# SCH_Aether_Zero_R0_4.net
KiCad netlist of a schematic drawn in EasyEDA
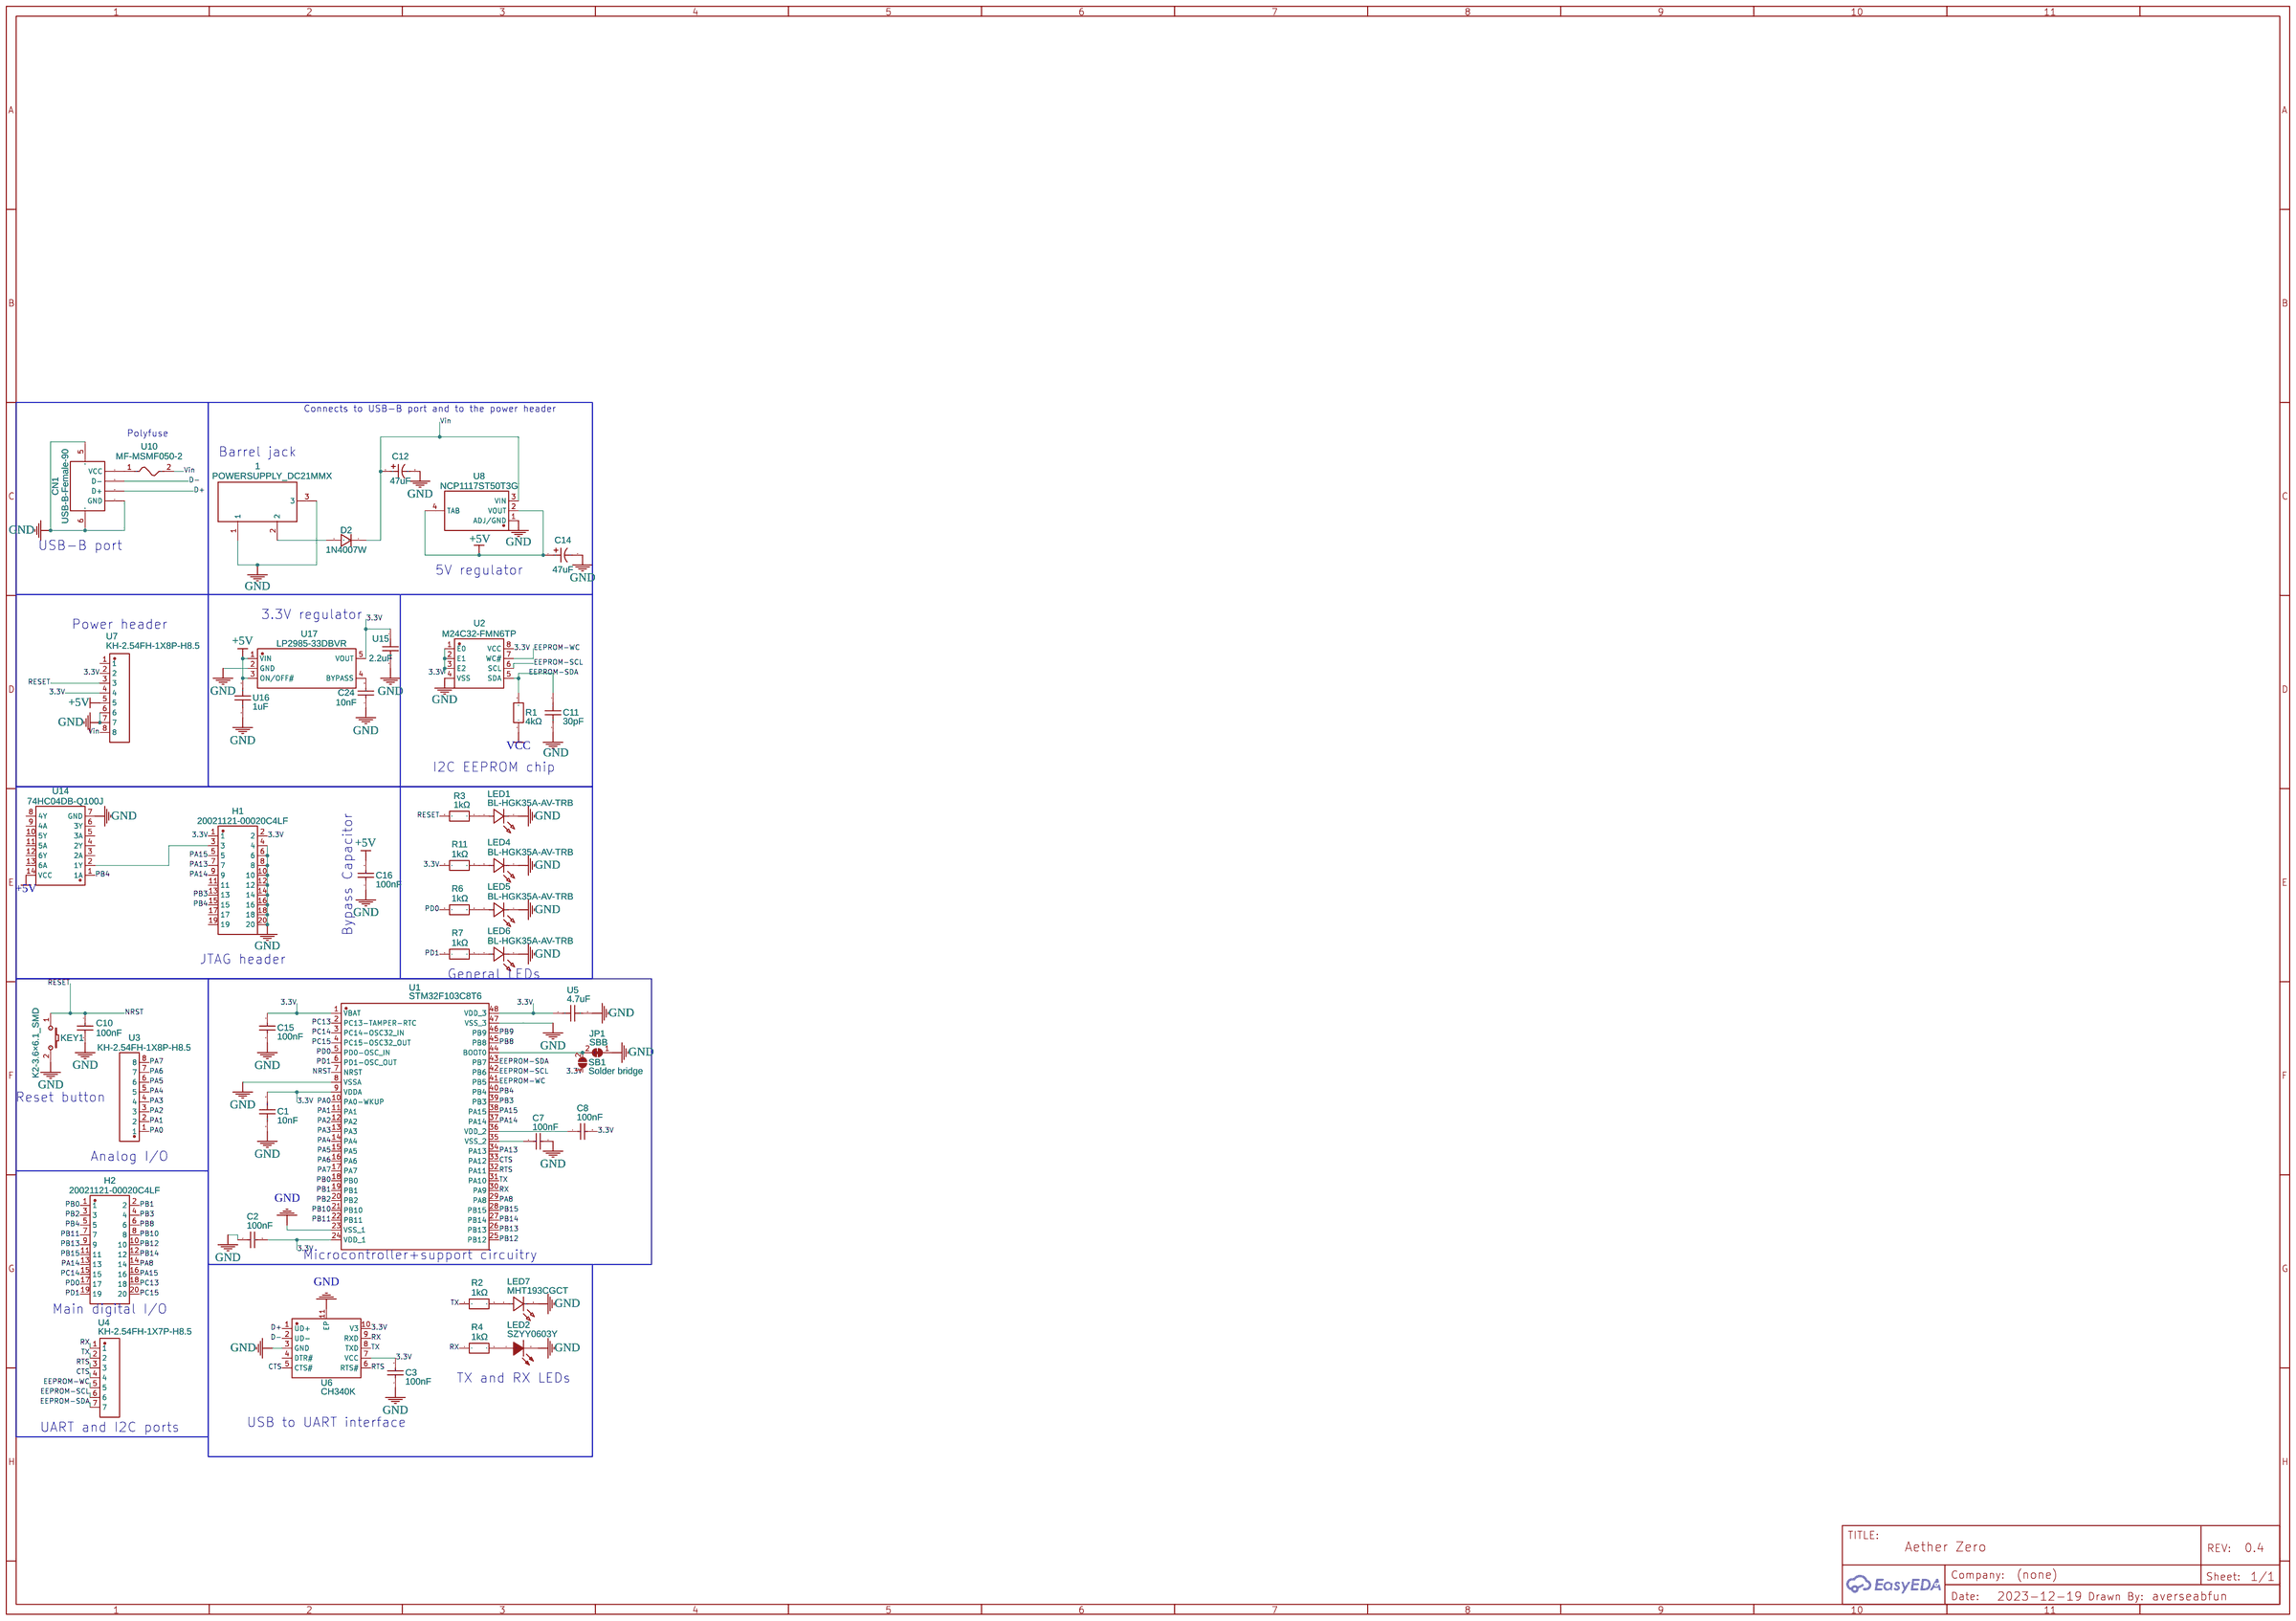
[diagram p0: schematic sheet]

(export (version "E")
  (design (tool "Eeschema 10.0.6"))
  (components
    (comp (ref "1") (value "POWERSUPPLY_DC21MMX") (libsource (lib "") (part "POWERSUPPLY_DC21MMX")))
    (comp (ref "C1")
      (value "10nF")
      (fields
        (field (name "Manufacturer Part") "CC0805KRX7R8BB103")
        (field (name "Manufacturer") "YAGEO(国巨)")
      )
      (libsource (lib "") (part "CC0805KRX7R8BB103"))
    )
    (comp (ref "C2")
      (value "100nF")
      (fields (field (name "Manufacturer Part") "0402B104K160NT") (field (name "Manufacturer") "FH(风华)"))
      (libsource (lib "") (part "0402B104K160NT_1"))
    )
    (comp (ref "C3")
      (value "100nF")
      (fields (field (name "Manufacturer Part") "0402B104K160NT") (field (name "Manufacturer") "FH(风华)"))
      (libsource (lib "") (part "0402B104K160NT_2"))
    )
    (comp (ref "C7")
      (value "100nF")
      (fields (field (name "Manufacturer Part") "0402B104K160NT") (field (name "Manufacturer") "FH(风华)"))
      (libsource (lib "") (part "0402B104K160NT_1"))
    )
    (comp (ref "C8")
      (value "100nF")
      (fields (field (name "Manufacturer Part") "0402B104K160NT") (field (name "Manufacturer") "FH(风华)"))
      (libsource (lib "") (part "0402B104K160NT_1"))
    )
    (comp (ref "C10")
      (value "100nF")
      (fields (field (name "Manufacturer Part") "0402B104K160NT") (field (name "Manufacturer") "FH(风华)"))
      (libsource (lib "") (part "0402B104K160NT"))
    )
    (comp (ref "C11")
      (value "30pF")
      (fields
        (field (name "Manufacturer Part") "AC0402JRNPO9BN300")
        (field (name "Manufacturer") "YAGEO(国巨)")
      )
      (libsource (lib "") (part "AC0402JRNPO9BN300"))
    )
    (comp (ref "C12")
      (value "47uF")
      (fields
        (field (name "Manufacturer Part") "RVT47UF35V67RV0039")
        (field (name "Manufacturer") "KNSCHA(科尼盛)")
      )
      (libsource (lib "") (part "RVT47UF35V67RV0039"))
    )
    (comp (ref "C14")
      (value "47uF")
      (fields
        (field (name "Manufacturer Part") "RVT47UF35V67RV0039")
        (field (name "Manufacturer") "KNSCHA(科尼盛)")
      )
      (libsource (lib "") (part "RVT47UF35V67RV0039"))
    )
    (comp (ref "C15")
      (value "100nF")
      (fields (field (name "Manufacturer Part") "0402B104K160NT") (field (name "Manufacturer") "FH(风华)"))
      (libsource (lib "") (part "0402B104K160NT"))
    )
    (comp (ref "C16")
      (value "100nF")
      (fields (field (name "Manufacturer Part") "0402B104K160NT") (field (name "Manufacturer") "FH(风华)"))
      (libsource (lib "") (part "0402B104K160NT_2"))
    )
    (comp (ref "C24")
      (value "10nF")
      (fields (field (name "Manufacturer Part") "0402B103K500NT") (field (name "Manufacturer") "FH(风华)"))
      (libsource (lib "") (part "0402B103K500NT"))
    )
    (comp (ref "CN1")
      (value "USB-B-Female-90")
      (fields (field (name "Manufacturer Part") "921-111A1010D10200") (field (name "Manufacturer") "精拓金"))
      (libsource (lib "") (part "USB-B-Female-90"))
    )
    (comp (ref "D2")
      (value "1N4007W")
      (fields (field (name "Manufacturer") "BLUE ROCKET"))
      (libsource (lib "") (part "1N4007W"))
    )
    (comp (ref "H1")
      (value "20021121-00020C4LF")
      (fields (field (name "Manufacturer") "Amphenol"))
      (libsource (lib "") (part "20021121-00020C4LF"))
    )
    (comp (ref "H2")
      (value "20021121-00020C4LF")
      (fields (field (name "Manufacturer") "Amphenol"))
      (libsource (lib "") (part "20021121-00020C4LF"))
    )
    (comp (ref "JP1") (value "SBB") (libsource (lib "") (part "SBB")))
    (comp (ref "KEY1")
      (value "K2-3.6×6.1_SMD")
      (fields (field (name "Manufacturer Part") "K2-1107ST-A4SW-06"))
      (libsource (lib "") (part "K2-3.6×6.1_SMD"))
    )
    (comp (ref "LED1")
      (value "BL-HGK35A-AV-TRB")
      (fields (field (name "Manufacturer") "BrtLed(佰鸿)"))
      (libsource (lib "") (part "BL-HGK35A-AV-TRB"))
    )
    (comp (ref "LED2")
      (value "SZYY0603Y")
      (fields (field (name "Manufacturer") "yongyu(永裕光电)"))
      (libsource (lib "") (part "SZYY0603Y"))
    )
    (comp (ref "LED4")
      (value "BL-HGK35A-AV-TRB")
      (fields (field (name "Manufacturer") "BrtLed(佰鸿)"))
      (libsource (lib "") (part "BL-HGK35A-AV-TRB"))
    )
    (comp (ref "LED5")
      (value "BL-HGK35A-AV-TRB")
      (fields (field (name "Manufacturer") "BrtLed(佰鸿)"))
      (libsource (lib "") (part "BL-HGK35A-AV-TRB"))
    )
    (comp (ref "LED6")
      (value "BL-HGK35A-AV-TRB")
      (fields (field (name "Manufacturer") "BrtLed(佰鸿)"))
      (libsource (lib "") (part "BL-HGK35A-AV-TRB"))
    )
    (comp (ref "LED7")
      (value "MHT193CGCT")
      (fields (field (name "Manufacturer") "MEIHUA(美华)"))
      (libsource (lib "") (part "MHT193CGCT"))
    )
    (comp (ref "R1")
      (value "4kΩ")
      (fields (field (name "Manufacturer Part") "RN732BTTD4001B25") (field (name "Manufacturer") "KOA"))
      (libsource (lib "") (part "RN732BTTD4001B25"))
    )
    (comp (ref "R2")
      (value "1kΩ")
      (fields (field (name "Manufacturer Part") "CR-03JA7----1K") (field (name "Manufacturer") "Viking Tech"))
      (libsource (lib "") (part "CR-03JA7----1K"))
    )
    (comp (ref "R3")
      (value "1kΩ")
      (fields (field (name "Manufacturer Part") "CR-03JA7----1K") (field (name "Manufacturer") "Viking Tech"))
      (libsource (lib "") (part "CR-03JA7----1K_1"))
    )
    (comp (ref "R4")
      (value "1kΩ")
      (fields (field (name "Manufacturer Part") "CR-03JA7----1K") (field (name "Manufacturer") "Viking Tech"))
      (libsource (lib "") (part "CR-03JA7----1K"))
    )
    (comp (ref "R6")
      (value "1kΩ")
      (fields (field (name "Manufacturer Part") "CR-03JA7----1K") (field (name "Manufacturer") "Viking Tech"))
      (libsource (lib "") (part "CR-03JA7----1K"))
    )
    (comp (ref "R7")
      (value "1kΩ")
      (fields (field (name "Manufacturer Part") "CR-03JA7----1K") (field (name "Manufacturer") "Viking Tech"))
      (libsource (lib "") (part "CR-03JA7----1K"))
    )
    (comp (ref "R11")
      (value "1kΩ")
      (fields (field (name "Manufacturer Part") "CR-03JA7----1K") (field (name "Manufacturer") "Viking Tech"))
      (libsource (lib "") (part "CR-03JA7----1K"))
    )
    (comp (ref "SB1")
      (value "Solder bridge")
      (fields (field (name "Manufacturer Part") "DNP"))
      (libsource (lib "") (part "Solder bridge"))
    )
    (comp (ref "U1")
      (value "STM32F103C8T6")
      (fields (field (name "Manufacturer") "ST(意法半导体)"))
      (libsource (lib "") (part "STM32F103C8T6"))
    )
    (comp (ref "U2")
      (value "M24C32-FMN6TP")
      (fields (field (name "Manufacturer") "ST(意法半导体)"))
      (libsource (lib "") (part "M24C32-FMN6TP"))
    )
    (comp (ref "U3")
      (value "KH-2.54FH-1X8P-H8.5")
      (fields (field (name "Manufacturer") "kinghelm(金航标)"))
      (libsource (lib "") (part "KH-2.54FH-1X8P-H8.5_1"))
    )
    (comp (ref "U4")
      (value "KH-2.54FH-1X7P-H8.5")
      (fields (field (name "Manufacturer") "kinghelm(金航标)"))
      (libsource (lib "") (part "KH-2.54FH-1X7P-H8.5"))
    )
    (comp (ref "U5")
      (value "4.7uF")
      (fields
        (field (name "Manufacturer Part") "CSA0603X5R475K6R3JT")
        (field (name "Manufacturer") "HRE(芯声)")
      )
      (libsource (lib "") (part "CSA0603X5R475K6R3JT"))
    )
    (comp (ref "U6")
      (value "CH340K")
      (fields (field (name "Manufacturer") "WCH(南京沁恒)"))
      (libsource (lib "") (part "CH340K"))
    )
    (comp (ref "U7")
      (value "KH-2.54FH-1X8P-H8.5")
      (fields (field (name "Manufacturer") "kinghelm(金航标)"))
      (libsource (lib "") (part "KH-2.54FH-1X8P-H8.5"))
    )
    (comp (ref "U8")
      (value "NCP1117ST50T3G")
      (fields (field (name "Manufacturer") "onsemi(安森美)"))
      (libsource (lib "") (part "NCP1117ST50T3G"))
    )
    (comp (ref "U10")
      (value "MF-MSMF050-2")
      (fields (field (name "Manufacturer") "BOURNS"))
      (libsource (lib "") (part "MF-MSMF050-2"))
    )
    (comp (ref "U14")
      (value "74HC04DB-Q100J")
      (fields (field (name "Manufacturer") "Nexperia(安世)"))
      (libsource (lib "") (part "74HC04DB-Q100J"))
    )
    (comp (ref "U15")
      (value "2.2uF")
      (fields (field (name "Manufacturer Part") "0805X225K250CT") (field (name "Manufacturer") "Walsin(华新科)"))
      (libsource (lib "") (part "0805X225K250CT_C5122273"))
    )
    (comp (ref "U16")
      (value "1uF")
      (fields (field (name "Manufacturer Part") "CGA5L3X8R1H105KT0Y0N") (field (name "Manufacturer") "TDK"))
      (libsource (lib "") (part "CGA5L3X8R1H105KT0Y0N"))
    )
    (comp (ref "U17")
      (value "LP2985-33DBVR")
      (fields (field (name "Manufacturer") "TI(德州仪器)"))
      (libsource (lib "") (part "LP2985-33DBVR"))
    )
  )
  (nets
    (net (code "1") (name "+5V") (class "Default")
      (node (ref "C14") (pin "1") (pinfunction "1_1") (pintype "input"))
      (node (ref "C16") (pin "2") (pinfunction "2_2") (pintype "input"))
      (node (ref "U14") (pin "14") (pinfunction "VCC_14") (pintype "unspecified"))
      (node (ref "U16") (pin "2") (pinfunction "2_2") (pintype "unspecified"))
      (node (ref "U17") (pin "1") (pinfunction "VIN_1") (pintype "unspecified"))
      (node (ref "U17") (pin "3") (pinfunction "ON/OFF#_3") (pintype "unspecified"))
      (node (ref "U7") (pin "5") (pinfunction "5_5") (pintype "unspecified"))
      (node (ref "U8") (pin "2") (pinfunction "VOUT_2") (pintype "unspecified"))
      (node (ref "U8") (pin "4") (pinfunction "TAB_4") (pintype "unspecified"))
    )
    (net (code "2") (name "/3.3V") (class "Default")
      (node (ref "C1") (pin "2") (pinfunction "2_2") (pintype "unspecified"))
      (node (ref "C15") (pin "1") (pinfunction "1_1") (pintype "input"))
      (node (ref "C2") (pin "2") (pinfunction "2_2") (pintype "input"))
      (node (ref "C3") (pin "2") (pinfunction "2_2") (pintype "input"))
      (node (ref "C8") (pin "2") (pinfunction "2_2") (pintype "input"))
      (node (ref "H1") (pin "1") (pinfunction "1_1") (pintype "unspecified"))
      (node (ref "H1") (pin "2") (pinfunction "2_2") (pintype "unspecified"))
      (node (ref "R11") (pin "1") (pinfunction "1_1") (pintype "unspecified"))
      (node (ref "SB1") (pin "1") (pinfunction "A_1") (pintype "unspecified"))
      (node (ref "U1") (pin "1") (pinfunction "VBAT_1") (pintype "unspecified"))
      (node (ref "U1") (pin "24") (pinfunction "VDD_1_24") (pintype "unspecified"))
      (node (ref "U1") (pin "48") (pinfunction "VDD_3_48") (pintype "unspecified"))
      (node (ref "U1") (pin "9") (pinfunction "VDDA_9") (pintype "unspecified"))
      (node (ref "U15") (pin "1") (pinfunction "1_1") (pintype "unspecified"))
      (node (ref "U17") (pin "5") (pinfunction "VOUT_5") (pintype "unspecified"))
      (node (ref "U2") (pin "1") (pinfunction "E0_1") (pintype "unspecified"))
      (node (ref "U2") (pin "2") (pinfunction "E1_2") (pintype "unspecified"))
      (node (ref "U2") (pin "3") (pinfunction "E2_3") (pintype "unspecified"))
      (node (ref "U2") (pin "8") (pinfunction "VCC_8") (pintype "unspecified"))
      (node (ref "U5") (pin "1") (pinfunction "1_1") (pintype "unspecified"))
      (node (ref "U6") (pin "10") (pinfunction "V3_10") (pintype "unspecified"))
      (node (ref "U6") (pin "7") (pinfunction "VCC_7") (pintype "unspecified"))
      (node (ref "U7") (pin "2") (pinfunction "2_2") (pintype "unspecified"))
      (node (ref "U7") (pin "4") (pinfunction "4_4") (pintype "unspecified"))
    )
    (net (code "3") (name "/CTS") (class "Default")
      (node (ref "U1") (pin "33") (pinfunction "PA12_33") (pintype "unspecified"))
      (node (ref "U4") (pin "4") (pinfunction "4_4") (pintype "unspecified"))
      (node (ref "U6") (pin "5") (pinfunction "CTS#_5") (pintype "unspecified"))
    )
    (net (code "4") (name "/D+") (class "Default")
      (node (ref "CN1") (pin "3") (pinfunction "D+_3") (pintype "input"))
      (node (ref "U6") (pin "1") (pinfunction "UD+_1") (pintype "unspecified"))
    )
    (net (code "5") (name "/D-") (class "Default")
      (node (ref "CN1") (pin "2") (pinfunction "D-_2") (pintype "input"))
      (node (ref "U6") (pin "2") (pinfunction "UD-_2") (pintype "unspecified"))
    )
    (net (code "6") (name "/EEPROM-SCL") (class "Default")
      (node (ref "U1") (pin "42") (pinfunction "PB6_42") (pintype "unspecified"))
      (node (ref "U2") (pin "6") (pinfunction "SCL_6") (pintype "unspecified"))
      (node (ref "U4") (pin "6") (pinfunction "6_6") (pintype "unspecified"))
    )
    (net (code "7") (name "/EEPROM-SDA") (class "Default")
      (node (ref "C11") (pin "1") (pinfunction "1_1") (pintype "unspecified"))
      (node (ref "R1") (pin "2") (pinfunction "2_2") (pintype "unspecified"))
      (node (ref "U1") (pin "43") (pinfunction "PB7_43") (pintype "unspecified"))
      (node (ref "U2") (pin "5") (pinfunction "SDA_5") (pintype "unspecified"))
      (node (ref "U4") (pin "7") (pinfunction "7_7") (pintype "unspecified"))
    )
    (net (code "8") (name "/EEPROM-WC") (class "Default")
      (node (ref "U1") (pin "41") (pinfunction "PB5_41") (pintype "unspecified"))
      (node (ref "U2") (pin "7") (pinfunction "WC#_7") (pintype "unspecified"))
      (node (ref "U4") (pin "5") (pinfunction "5_5") (pintype "unspecified"))
    )
    (net (code "9") (name "/NRST") (class "Default")
      (node (ref "C10") (pin "1") (pinfunction "1_1") (pintype "input"))
      (node (ref "KEY1") (pin "1") (pinfunction "1_1") (pintype "unspecified"))
      (node (ref "R3") (pin "2") (pinfunction "2_2") (pintype "unspecified"))
      (node (ref "U1") (pin "7") (pinfunction "NRST_7") (pintype "unspecified"))
      (node (ref "U7") (pin "3") (pinfunction "3_3") (pintype "unspecified"))
    )
    (net (code "10") (name "/PA0") (class "Default")
      (node (ref "U1") (pin "10") (pinfunction "PA0-WKUP_10") (pintype "unspecified"))
      (node (ref "U3") (pin "1") (pinfunction "1_1") (pintype "unspecified"))
    )
    (net (code "11") (name "/PA1") (class "Default")
      (node (ref "U1") (pin "11") (pinfunction "PA1_11") (pintype "unspecified"))
      (node (ref "U3") (pin "2") (pinfunction "2_2") (pintype "unspecified"))
    )
    (net (code "12") (name "/PA2") (class "Default")
      (node (ref "U1") (pin "12") (pinfunction "PA2_12") (pintype "unspecified"))
      (node (ref "U3") (pin "3") (pinfunction "3_3") (pintype "unspecified"))
    )
    (net (code "13") (name "/PA3") (class "Default")
      (node (ref "U1") (pin "13") (pinfunction "PA3_13") (pintype "unspecified"))
      (node (ref "U3") (pin "4") (pinfunction "4_4") (pintype "unspecified"))
    )
    (net (code "14") (name "/PA4") (class "Default")
      (node (ref "U1") (pin "14") (pinfunction "PA4_14") (pintype "unspecified"))
      (node (ref "U3") (pin "5") (pinfunction "5_5") (pintype "unspecified"))
    )
    (net (code "15") (name "/PA5") (class "Default")
      (node (ref "U1") (pin "15") (pinfunction "PA5_15") (pintype "unspecified"))
      (node (ref "U3") (pin "6") (pinfunction "6_6") (pintype "unspecified"))
    )
    (net (code "16") (name "/PA6") (class "Default")
      (node (ref "U1") (pin "16") (pinfunction "PA6_16") (pintype "unspecified"))
      (node (ref "U3") (pin "7") (pinfunction "7_7") (pintype "unspecified"))
    )
    (net (code "17") (name "/PA7") (class "Default")
      (node (ref "U1") (pin "17") (pinfunction "PA7_17") (pintype "unspecified"))
      (node (ref "U3") (pin "8") (pinfunction "8_8") (pintype "unspecified"))
    )
    (net (code "18") (name "/PA8") (class "Default")
      (node (ref "H2") (pin "14") (pinfunction "14_14") (pintype "unspecified"))
      (node (ref "U1") (pin "29") (pinfunction "PA8_29") (pintype "unspecified"))
    )
    (net (code "19") (name "/PA13") (class "Default")
      (node (ref "H1") (pin "7") (pinfunction "7_7") (pintype "unspecified"))
      (node (ref "U1") (pin "34") (pinfunction "PA13_34") (pintype "unspecified"))
    )
    (net (code "20") (name "/PA14") (class "Default")
      (node (ref "H1") (pin "9") (pinfunction "9_9") (pintype "unspecified"))
      (node (ref "H2") (pin "13") (pinfunction "13_13") (pintype "unspecified"))
      (node (ref "U1") (pin "37") (pinfunction "PA14_37") (pintype "unspecified"))
    )
    (net (code "21") (name "/PA15") (class "Default")
      (node (ref "H1") (pin "5") (pinfunction "5_5") (pintype "unspecified"))
      (node (ref "H2") (pin "16") (pinfunction "16_16") (pintype "unspecified"))
      (node (ref "U1") (pin "38") (pinfunction "PA15_38") (pintype "unspecified"))
    )
    (net (code "22") (name "/PB0") (class "Default")
      (node (ref "H2") (pin "1") (pinfunction "1_1") (pintype "unspecified"))
      (node (ref "U1") (pin "18") (pinfunction "PB0_18") (pintype "unspecified"))
    )
    (net (code "23") (name "/PB1") (class "Default")
      (node (ref "H2") (pin "2") (pinfunction "2_2") (pintype "unspecified"))
      (node (ref "U1") (pin "19") (pinfunction "PB1_19") (pintype "unspecified"))
    )
    (net (code "24") (name "/PB2") (class "Default")
      (node (ref "H2") (pin "3") (pinfunction "3_3") (pintype "unspecified"))
      (node (ref "U1") (pin "20") (pinfunction "PB2_20") (pintype "unspecified"))
    )
    (net (code "25") (name "/PB3") (class "Default")
      (node (ref "H1") (pin "13") (pinfunction "13_13") (pintype "unspecified"))
      (node (ref "H2") (pin "4") (pinfunction "4_4") (pintype "unspecified"))
      (node (ref "U1") (pin "39") (pinfunction "PB3_39") (pintype "unspecified"))
    )
    (net (code "26") (name "/PB4") (class "Default")
      (node (ref "H1") (pin "15") (pinfunction "15_15") (pintype "unspecified"))
      (node (ref "H2") (pin "5") (pinfunction "5_5") (pintype "unspecified"))
      (node (ref "U1") (pin "40") (pinfunction "PB4_40") (pintype "unspecified"))
      (node (ref "U14") (pin "1") (pinfunction "1A_1") (pintype "unspecified"))
    )
    (net (code "27") (name "/PB8") (class "Default")
      (node (ref "H2") (pin "6") (pinfunction "6_6") (pintype "unspecified"))
      (node (ref "U1") (pin "45") (pinfunction "PB8_45") (pintype "unspecified"))
    )
    (net (code "28") (name "/PB9") (class "Default")
      (node (ref "U1") (pin "46") (pinfunction "PB9_46") (pintype "unspecified"))
    )
    (net (code "29") (name "/PB10") (class "Default")
      (node (ref "H2") (pin "8") (pinfunction "8_8") (pintype "unspecified"))
      (node (ref "U1") (pin "21") (pinfunction "PB10_21") (pintype "unspecified"))
    )
    (net (code "30") (name "/PB11") (class "Default")
      (node (ref "H2") (pin "7") (pinfunction "7_7") (pintype "unspecified"))
      (node (ref "U1") (pin "22") (pinfunction "PB11_22") (pintype "unspecified"))
    )
    (net (code "31") (name "/PB12") (class "Default")
      (node (ref "H2") (pin "10") (pinfunction "10_10") (pintype "unspecified"))
      (node (ref "U1") (pin "25") (pinfunction "PB12_25") (pintype "unspecified"))
    )
    (net (code "32") (name "/PB13") (class "Default")
      (node (ref "H2") (pin "9") (pinfunction "9_9") (pintype "unspecified"))
      (node (ref "U1") (pin "26") (pinfunction "PB13_26") (pintype "unspecified"))
    )
    (net (code "33") (name "/PB14") (class "Default")
      (node (ref "H2") (pin "12") (pinfunction "12_12") (pintype "unspecified"))
      (node (ref "U1") (pin "27") (pinfunction "PB14_27") (pintype "unspecified"))
    )
    (net (code "34") (name "/PB15") (class "Default")
      (node (ref "H2") (pin "11") (pinfunction "11_11") (pintype "unspecified"))
      (node (ref "U1") (pin "28") (pinfunction "PB15_28") (pintype "unspecified"))
    )
    (net (code "35") (name "/PC13") (class "Default")
      (node (ref "H2") (pin "18") (pinfunction "18_18") (pintype "unspecified"))
      (node (ref "U1") (pin "2") (pinfunction "PC13-TAMPER-RTC_2") (pintype "unspecified"))
    )
    (net (code "36") (name "/PC14") (class "Default")
      (node (ref "H2") (pin "15") (pinfunction "15_15") (pintype "unspecified"))
      (node (ref "U1") (pin "3") (pinfunction "PC14-OSC32_IN_3") (pintype "unspecified"))
    )
    (net (code "37") (name "/PC15") (class "Default")
      (node (ref "H2") (pin "20") (pinfunction "20_20") (pintype "unspecified"))
      (node (ref "U1") (pin "4") (pinfunction "PC15-OSC32_OUT_4") (pintype "unspecified"))
    )
    (net (code "38") (name "/PD0") (class "Default")
      (node (ref "H2") (pin "17") (pinfunction "17_17") (pintype "unspecified"))
      (node (ref "R6") (pin "1") (pinfunction "1_1") (pintype "unspecified"))
      (node (ref "U1") (pin "5") (pinfunction "PD0-OSC_IN_5") (pintype "unspecified"))
    )
    (net (code "39") (name "/PD1") (class "Default")
      (node (ref "H2") (pin "19") (pinfunction "19_19") (pintype "unspecified"))
      (node (ref "R7") (pin "1") (pinfunction "1_1") (pintype "unspecified"))
      (node (ref "U1") (pin "6") (pinfunction "PD1-OSC_OUT_6") (pintype "unspecified"))
    )
    (net (code "40") (name "/RTS") (class "Default")
      (node (ref "U1") (pin "32") (pinfunction "PA11_32") (pintype "unspecified"))
      (node (ref "U4") (pin "3") (pinfunction "3_3") (pintype "unspecified"))
      (node (ref "U6") (pin "6") (pinfunction "RTS#_6") (pintype "unspecified"))
    )
    (net (code "41") (name "/RX") (class "Default")
      (node (ref "R4") (pin "1") (pinfunction "1_1") (pintype "unspecified"))
      (node (ref "U1") (pin "30") (pinfunction "PA9_30") (pintype "unspecified"))
      (node (ref "U4") (pin "1") (pinfunction "1_1") (pintype "unspecified"))
      (node (ref "U6") (pin "9") (pinfunction "RXD_9") (pintype "unspecified"))
    )
    (net (code "42") (name "/TX") (class "Default")
      (node (ref "R2") (pin "1") (pinfunction "1_1") (pintype "unspecified"))
      (node (ref "U1") (pin "31") (pinfunction "PA10_31") (pintype "unspecified"))
      (node (ref "U4") (pin "2") (pinfunction "2_2") (pintype "unspecified"))
      (node (ref "U6") (pin "8") (pinfunction "TXD_8") (pintype "unspecified"))
    )
    (net (code "43") (name "/Vin") (class "Default")
      (node (ref "C12") (pin "1") (pinfunction "1_1") (pintype "input"))
      (node (ref "D2") (pin "1") (pinfunction "1_1") (pintype "unspecified"))
      (node (ref "U10") (pin "2") (pinfunction "2_2") (pintype "unspecified"))
      (node (ref "U7") (pin "8") (pinfunction "8_8") (pintype "unspecified"))
      (node (ref "U8") (pin "3") (pinfunction "VIN_3") (pintype "unspecified"))
    )
    (net (code "44") (name "GND") (class "Default")
      (node (ref "1") (pin "1") (pinfunction "1_1") (pintype "bidirectional"))
      (node (ref "1") (pin "3") (pinfunction "3_3") (pintype "bidirectional"))
      (node (ref "C1") (pin "1") (pinfunction "1_1") (pintype "unspecified"))
      (node (ref "C10") (pin "2") (pinfunction "2_2") (pintype "input"))
      (node (ref "C11") (pin "2") (pinfunction "2_2") (pintype "unspecified"))
      (node (ref "C12") (pin "2") (pinfunction "2_2") (pintype "input"))
      (node (ref "C14") (pin "2") (pinfunction "2_2") (pintype "input"))
      (node (ref "C15") (pin "2") (pinfunction "2_2") (pintype "input"))
      (node (ref "C16") (pin "1") (pinfunction "1_1") (pintype "input"))
      (node (ref "C2") (pin "1") (pinfunction "1_1") (pintype "input"))
      (node (ref "C24") (pin "1") (pinfunction "1_1") (pintype "input"))
      (node (ref "C3") (pin "1") (pinfunction "1_1") (pintype "input"))
      (node (ref "C7") (pin "2") (pinfunction "2_2") (pintype "input"))
      (node (ref "CN1") (pin "4") (pinfunction "GND_4") (pintype "input"))
      (node (ref "CN1") (pin "5") (pinfunction "SH1_5") (pintype "unspecified"))
      (node (ref "CN1") (pin "6") (pinfunction "SH2_6") (pintype "unspecified"))
      (node (ref "H1") (pin "10") (pinfunction "10_10") (pintype "unspecified"))
      (node (ref "H1") (pin "12") (pinfunction "12_12") (pintype "unspecified"))
      (node (ref "H1") (pin "14") (pinfunction "14_14") (pintype "unspecified"))
      (node (ref "H1") (pin "16") (pinfunction "16_16") (pintype "unspecified"))
      (node (ref "H1") (pin "18") (pinfunction "18_18") (pintype "unspecified"))
      (node (ref "H1") (pin "20") (pinfunction "20_20") (pintype "unspecified"))
      (node (ref "H1") (pin "4") (pinfunction "4_4") (pintype "unspecified"))
      (node (ref "H1") (pin "6") (pinfunction "6_6") (pintype "unspecified"))
      (node (ref "H1") (pin "8") (pinfunction "8_8") (pintype "unspecified"))
      (node (ref "JP1") (pin "1") (pinfunction "A_1") (pintype "unspecified"))
      (node (ref "KEY1") (pin "2") (pinfunction "2_2") (pintype "unspecified"))
      (node (ref "LED1") (pin "1") (pinfunction "K_1") (pintype "unspecified"))
      (node (ref "LED2") (pin "2") (pinfunction "-_2") (pintype "unspecified"))
      (node (ref "LED4") (pin "1") (pinfunction "K_1") (pintype "unspecified"))
      (node (ref "LED5") (pin "1") (pinfunction "K_1") (pintype "unspecified"))
      (node (ref "LED6") (pin "1") (pinfunction "K_1") (pintype "unspecified"))
      (node (ref "LED7") (pin "1") (pinfunction "K_1") (pintype "unspecified"))
      (node (ref "U1") (pin "23") (pinfunction "VSS_1_23") (pintype "unspecified"))
      (node (ref "U1") (pin "47") (pinfunction "VSS_3_47") (pintype "unspecified"))
      (node (ref "U1") (pin "8") (pinfunction "VSSA_8") (pintype "unspecified"))
      (node (ref "U14") (pin "7") (pinfunction "GND_7") (pintype "unspecified"))
      (node (ref "U15") (pin "2") (pinfunction "2_2") (pintype "unspecified"))
      (node (ref "U16") (pin "1") (pinfunction "1_1") (pintype "unspecified"))
      (node (ref "U17") (pin "2") (pinfunction "GND_2") (pintype "unspecified"))
      (node (ref "U2") (pin "4") (pinfunction "VSS_4") (pintype "unspecified"))
      (node (ref "U5") (pin "2") (pinfunction "2_2") (pintype "unspecified"))
      (node (ref "U6") (pin "11") (pinfunction "EP_11") (pintype "unspecified"))
      (node (ref "U6") (pin "3") (pinfunction "GND_3") (pintype "unspecified"))
      (node (ref "U7") (pin "6") (pinfunction "6_6") (pintype "unspecified"))
      (node (ref "U7") (pin "7") (pinfunction "7_7") (pintype "unspecified"))
      (node (ref "U8") (pin "1") (pinfunction "ADJ/GND_1") (pintype "unspecified"))
    )
    (net (code "45") (name "Net-(1-Pad2)") (class "Default")
      (node (ref "1") (pin "2") (pinfunction "2_2") (pintype "bidirectional"))
      (node (ref "D2") (pin "2") (pinfunction "2_2") (pintype "unspecified"))
    )
    (net (code "46") (name "Net-(CN1-VCC)") (class "Default")
      (node (ref "CN1") (pin "1") (pinfunction "VCC_1") (pintype "input"))
      (node (ref "U10") (pin "1") (pinfunction "1_1") (pintype "unspecified"))
    )
    (net (code "47") (name "Net-(JP1-B)") (class "Default")
      (node (ref "JP1") (pin "2") (pinfunction "B_2") (pintype "unspecified"))
      (node (ref "SB1") (pin "2") (pinfunction "B_2") (pintype "unspecified"))
      (node (ref "U1") (pin "44") (pinfunction "BOOT0_44") (pintype "unspecified"))
    )
    (net (code "48") (name "Net-(LED1-A)") (class "Default")
      (node (ref "LED1") (pin "2") (pinfunction "A_2") (pintype "unspecified"))
      (node (ref "R3") (pin "1") (pinfunction "1_1") (pintype "unspecified"))
    )
    (net (code "49") (name "Net-(LED2-+)") (class "Default")
      (node (ref "LED2") (pin "1") (pinfunction "+_1") (pintype "unspecified"))
      (node (ref "R4") (pin "2") (pinfunction "2_2") (pintype "unspecified"))
    )
    (net (code "50") (name "Net-(LED4-A)") (class "Default")
      (node (ref "LED4") (pin "2") (pinfunction "A_2") (pintype "unspecified"))
      (node (ref "R11") (pin "2") (pinfunction "2_2") (pintype "unspecified"))
    )
    (net (code "51") (name "Net-(LED5-A)") (class "Default")
      (node (ref "LED5") (pin "2") (pinfunction "A_2") (pintype "unspecified"))
      (node (ref "R6") (pin "2") (pinfunction "2_2") (pintype "unspecified"))
    )
    (net (code "52") (name "Net-(LED6-A)") (class "Default")
      (node (ref "LED6") (pin "2") (pinfunction "A_2") (pintype "unspecified"))
      (node (ref "R7") (pin "2") (pinfunction "2_2") (pintype "unspecified"))
    )
    (net (code "53") (name "Net-(LED7-A)") (class "Default")
      (node (ref "LED7") (pin "2") (pinfunction "A_2") (pintype "unspecified"))
      (node (ref "R2") (pin "2") (pinfunction "2_2") (pintype "unspecified"))
    )
    (net (code "54") (name "Net-(U1-VDD_2)") (class "Default")
      (node (ref "C8") (pin "1") (pinfunction "1_1") (pintype "input"))
      (node (ref "U1") (pin "36") (pinfunction "VDD_2_36") (pintype "unspecified"))
    )
    (net (code "55") (name "Net-(U1-VSS_2)") (class "Default")
      (node (ref "C7") (pin "1") (pinfunction "1_1") (pintype "input"))
      (node (ref "U1") (pin "35") (pinfunction "VSS_2_35") (pintype "unspecified"))
    )
    (net (code "56") (name "Net-(U14-1Y)") (class "Default")
      (node (ref "H1") (pin "3") (pinfunction "3_3") (pintype "unspecified"))
      (node (ref "U14") (pin "2") (pinfunction "1Y_2") (pintype "unspecified"))
    )
    (net (code "57") (name "Net-(U17-BYPASS)") (class "Default")
      (node (ref "C24") (pin "2") (pinfunction "2_2") (pintype "input"))
      (node (ref "U17") (pin "4") (pinfunction "BYPASS_4") (pintype "unspecified"))
    )
    (net (code "58") (name "VCC") (class "Default")
      (node (ref "R1") (pin "1") (pinfunction "1_1") (pintype "unspecified"))
    )
    (net (code "59") (name "unconnected-(H1-Pad11)") (class "Default")
      (node (ref "H1") (pin "11") (pinfunction "11_11") (pintype "unspecified"))
    )
    (net (code "60") (name "unconnected-(H1-Pad17)") (class "Default")
      (node (ref "H1") (pin "17") (pinfunction "17_17") (pintype "unspecified"))
    )
    (net (code "61") (name "unconnected-(H1-Pad19)") (class "Default")
      (node (ref "H1") (pin "19") (pinfunction "19_19") (pintype "unspecified"))
    )
    (net (code "62") (name "unconnected-(U6-DTR#-Pad4)") (class "Default")
      (node (ref "U6") (pin "4") (pinfunction "DTR#_4") (pintype "unspecified"))
    )
    (net (code "63") (name "unconnected-(U7-Pad1)") (class "Default")
      (node (ref "U7") (pin "1") (pinfunction "1_1") (pintype "unspecified"))
    )
    (net (code "64") (name "unconnected-(U14-2A-Pad3)") (class "Default")
      (node (ref "U14") (pin "3") (pinfunction "2A_3") (pintype "unspecified"))
    )
    (net (code "65") (name "unconnected-(U14-2Y-Pad4)") (class "Default")
      (node (ref "U14") (pin "4") (pinfunction "2Y_4") (pintype "unspecified"))
    )
    (net (code "66") (name "unconnected-(U14-3A-Pad5)") (class "Default")
      (node (ref "U14") (pin "5") (pinfunction "3A_5") (pintype "unspecified"))
    )
    (net (code "67") (name "unconnected-(U14-3Y-Pad6)") (class "Default")
      (node (ref "U14") (pin "6") (pinfunction "3Y_6") (pintype "unspecified"))
    )
    (net (code "68") (name "unconnected-(U14-4A-Pad9)") (class "Default")
      (node (ref "U14") (pin "9") (pinfunction "4A_9") (pintype "unspecified"))
    )
    (net (code "69") (name "unconnected-(U14-4Y-Pad8)") (class "Default")
      (node (ref "U14") (pin "8") (pinfunction "4Y_8") (pintype "unspecified"))
    )
    (net (code "70") (name "unconnected-(U14-5A-Pad11)") (class "Default")
      (node (ref "U14") (pin "11") (pinfunction "5A_11") (pintype "unspecified"))
    )
    (net (code "71") (name "unconnected-(U14-5Y-Pad10)") (class "Default")
      (node (ref "U14") (pin "10") (pinfunction "5Y_10") (pintype "unspecified"))
    )
    (net (code "72") (name "unconnected-(U14-6A-Pad13)") (class "Default")
      (node (ref "U14") (pin "13") (pinfunction "6A_13") (pintype "unspecified"))
    )
    (net (code "73") (name "unconnected-(U14-6Y-Pad12)") (class "Default")
      (node (ref "U14") (pin "12") (pinfunction "6Y_12") (pintype "unspecified"))
    )
  )
)
